# Dev_BRD_STM32F030F4P6TR.net
KiCad netlist of a schematic drawn in Altium Designer
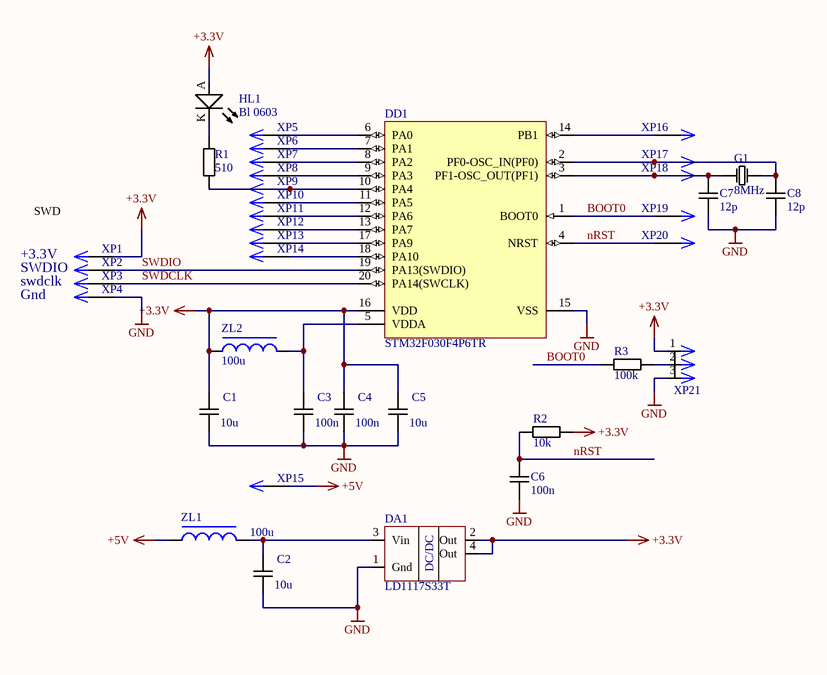
[diagram p0: Dev_BRD_STM32F030F4P6TR.SchDoc]

(export (version "E")
  (design (tool "Eeschema 10.0.6"))
  (components
    (comp (ref "C1")
      (value "10u")
      (footprint "CAPC1608(0603)N")
      (description "?")
      (fields (field (name "PART NUMBER") "CAPC1608(0603)"))
      (libsource (lib "SssAccesDatbase") (part "Cap"))
    )
    (comp (ref "C2")
      (value "10u")
      (footprint "CAPC1608(0603)N")
      (description "?")
      (fields (field (name "PART NUMBER") "CAPC1608(0603)"))
      (libsource (lib "SssAccesDatbase") (part "Cap"))
    )
    (comp (ref "C3")
      (value "100n")
      (footprint "CAPC1608(0603)N")
      (description "?")
      (fields (field (name "PART NUMBER") "CAPC1608(0603)"))
      (libsource (lib "SssAccesDatbase") (part "Cap"))
    )
    (comp (ref "C4")
      (value "100n")
      (footprint "CAPC1608(0603)N")
      (description "?")
      (fields (field (name "PART NUMBER") "CAPC1608(0603)"))
      (libsource (lib "SssAccesDatbase") (part "Cap"))
    )
    (comp (ref "C5")
      (value "10u")
      (footprint "CAPC1608(0603)N")
      (description "?")
      (fields (field (name "PART NUMBER") "CAPC1608(0603)"))
      (libsource (lib "SssAccesDatbase") (part "Cap"))
    )
    (comp (ref "C6")
      (value "100n")
      (footprint "CAPC1608(0603)N")
      (description "?")
      (fields (field (name "PART NUMBER") "CAPC1608(0603)"))
      (libsource (lib "SssAccesDatbase") (part "Cap"))
    )
    (comp (ref "C7")
      (value "12p")
      (footprint "CAPC1608(0603)N")
      (description "?")
      (fields (field (name "PART NUMBER") "CAPC1608(0603)"))
      (libsource (lib "SssAccesDatbase") (part "Cap"))
    )
    (comp (ref "C8")
      (value "12p")
      (footprint "CAPC1608(0603)N")
      (description "?")
      (fields (field (name "PART NUMBER") "CAPC1608(0603)"))
      (libsource (lib "SssAccesDatbase") (part "Cap"))
    )
    (comp (ref "DA1")
      (value "LD1117S33T")
      (footprint "SOT223_M")
      (description "LDO Voltage Regulators 3.3V 0.8A Positive")
      (fields (field (name "DIGI-KEY PART NUMBER") "?"))
      (libsource (lib "SssAccesDatbase") (part "LD1117S33T"))
    )
    (comp (ref "DD1")
      (value "STM32F030F4P6TR")
      (footprint "STM-TSSOP20_M")
      (description "ARM Microcontrollers - MCU Entry-level ARM Cortex-M0 Value MCU")
      (fields
        (field (name "PARTNUMBER") "STM32F030F4P6")
        (field (name "MOUSER PART NUMBER") "511-STM32F030F4P6TR")
      )
      (libsource (lib "SssAccesDatbase") (part "STM32F030F4P6"))
    )
    (comp (ref "G1")
      (value "8MHz")
      (footprint "HC-49/S")
      (description "Crystal HC-49/S")
      (libsource (lib "SssAccesDatbase") (part "Crystal"))
    )
    (comp (ref "HL1")
      (value "Bl 0603")
      (footprint "LED-0603-BLUE")
      (description "LED BLUE DIFFUSED 0603 SMD")
      (fields
        (field (name "PART NUMBER") "150060BS55040")
        (field (name "DIGI-KEY PART NUMBER") "732-12013-1-ND")
      )
      (libsource (lib "SssAccesDatbase") (part "LED"))
    )
    (comp (ref "R1")
      (value "510")
      (footprint "RESC1608(0603)N")
      (fields (field (name "PART NUMBER") "RESC1608(0603)") (field (name "DIGI-KEY PART NUMBER") "???"))
      (libsource (lib "") (part "Resistor general_2"))
    )
    (comp (ref "R2")
      (value "10k")
      (footprint "RESC1608(0603)N")
      (fields (field (name "PART NUMBER") "RESC1608(0603)") (field (name "DIGI-KEY PART NUMBER") "???"))
      (libsource (lib "SssAccesDatbase") (part "Resistor general"))
    )
    (comp (ref "R3")
      (value "100k")
      (footprint "RESC1608(0603)N")
      (fields (field (name "PART NUMBER") "RESC1608(0603)") (field (name "DIGI-KEY PART NUMBER") "???"))
      (libsource (lib "") (part "Resistor general_1"))
    )
    (comp (ref "XP1")
      (value "PLS-1")
      (footprint "PLS-1-3D")
      (description "CONN HEADER VERT 1POS")
      (fields
        (field (name "DIGI-KEY PART NUMBER") "S1011EC-01-ND")
        (field (name "MANUFACTURER PART NUMBER") "PRPC001SAAN-RC")
      )
      (libsource (lib "SssAccesDatbase") (part "XP-1_1"))
    )
    (comp (ref "XP2")
      (value "PLS-1")
      (footprint "PLS-1-3D")
      (description "CONN HEADER VERT 1POS")
      (fields
        (field (name "DIGI-KEY PART NUMBER") "S1011EC-01-ND")
        (field (name "MANUFACTURER PART NUMBER") "PRPC001SAAN-RC")
      )
      (libsource (lib "SssAccesDatbase") (part "XP-1_1"))
    )
    (comp (ref "XP3")
      (value "PLS-1")
      (footprint "PLS-1-3D")
      (description "CONN HEADER VERT 1POS")
      (fields
        (field (name "DIGI-KEY PART NUMBER") "S1011EC-01-ND")
        (field (name "MANUFACTURER PART NUMBER") "PRPC001SAAN-RC")
      )
      (libsource (lib "SssAccesDatbase") (part "XP-1_1"))
    )
    (comp (ref "XP4")
      (value "PLS-1")
      (footprint "PLS-1-3D")
      (description "CONN HEADER VERT 1POS")
      (fields
        (field (name "DIGI-KEY PART NUMBER") "S1011EC-01-ND")
        (field (name "MANUFACTURER PART NUMBER") "PRPC001SAAN-RC")
      )
      (libsource (lib "SssAccesDatbase") (part "XP-1_1"))
    )
    (comp (ref "XP5")
      (value "PLS-1")
      (footprint "PLS-1-3D")
      (description "CONN HEADER VERT 1POS")
      (fields
        (field (name "DIGI-KEY PART NUMBER") "S1011EC-01-ND")
        (field (name "MANUFACTURER PART NUMBER") "PRPC001SAAN-RC")
      )
      (libsource (lib "SssAccesDatbase") (part "XP-1_1"))
    )
    (comp (ref "XP6")
      (value "PLS-1")
      (footprint "PLS-1-3D")
      (description "CONN HEADER VERT 1POS")
      (fields
        (field (name "DIGI-KEY PART NUMBER") "S1011EC-01-ND")
        (field (name "MANUFACTURER PART NUMBER") "PRPC001SAAN-RC")
      )
      (libsource (lib "SssAccesDatbase") (part "XP-1_1"))
    )
    (comp (ref "XP7")
      (value "PLS-1")
      (footprint "PLS-1-3D")
      (description "CONN HEADER VERT 1POS")
      (fields
        (field (name "DIGI-KEY PART NUMBER") "S1011EC-01-ND")
        (field (name "MANUFACTURER PART NUMBER") "PRPC001SAAN-RC")
      )
      (libsource (lib "SssAccesDatbase") (part "XP-1_1"))
    )
    (comp (ref "XP8")
      (value "PLS-1")
      (footprint "PLS-1-3D")
      (description "CONN HEADER VERT 1POS")
      (fields
        (field (name "DIGI-KEY PART NUMBER") "S1011EC-01-ND")
        (field (name "MANUFACTURER PART NUMBER") "PRPC001SAAN-RC")
      )
      (libsource (lib "SssAccesDatbase") (part "XP-1_1"))
    )
    (comp (ref "XP9")
      (value "PLS-1")
      (footprint "PLS-1-3D")
      (description "CONN HEADER VERT 1POS")
      (fields
        (field (name "DIGI-KEY PART NUMBER") "S1011EC-01-ND")
        (field (name "MANUFACTURER PART NUMBER") "PRPC001SAAN-RC")
      )
      (libsource (lib "SssAccesDatbase") (part "XP-1_1"))
    )
    (comp (ref "XP10")
      (value "PLS-1")
      (footprint "PLS-1-3D")
      (description "CONN HEADER VERT 1POS")
      (fields
        (field (name "DIGI-KEY PART NUMBER") "S1011EC-01-ND")
        (field (name "MANUFACTURER PART NUMBER") "PRPC001SAAN-RC")
      )
      (libsource (lib "SssAccesDatbase") (part "XP-1_1"))
    )
    (comp (ref "XP11")
      (value "PLS-1")
      (footprint "PLS-1-3D")
      (description "CONN HEADER VERT 1POS")
      (fields
        (field (name "DIGI-KEY PART NUMBER") "S1011EC-01-ND")
        (field (name "MANUFACTURER PART NUMBER") "PRPC001SAAN-RC")
      )
      (libsource (lib "SssAccesDatbase") (part "XP-1_1"))
    )
    (comp (ref "XP12")
      (value "PLS-1")
      (footprint "PLS-1-3D")
      (description "CONN HEADER VERT 1POS")
      (fields
        (field (name "DIGI-KEY PART NUMBER") "S1011EC-01-ND")
        (field (name "MANUFACTURER PART NUMBER") "PRPC001SAAN-RC")
      )
      (libsource (lib "SssAccesDatbase") (part "XP-1_1"))
    )
    (comp (ref "XP13")
      (value "PLS-1")
      (footprint "PLS-1-3D")
      (description "CONN HEADER VERT 1POS")
      (fields
        (field (name "DIGI-KEY PART NUMBER") "S1011EC-01-ND")
        (field (name "MANUFACTURER PART NUMBER") "PRPC001SAAN-RC")
      )
      (libsource (lib "SssAccesDatbase") (part "XP-1_1"))
    )
    (comp (ref "XP14")
      (value "PLS-1")
      (footprint "PLS-1-3D")
      (description "CONN HEADER VERT 1POS")
      (fields
        (field (name "DIGI-KEY PART NUMBER") "S1011EC-01-ND")
        (field (name "MANUFACTURER PART NUMBER") "PRPC001SAAN-RC")
      )
      (libsource (lib "SssAccesDatbase") (part "XP-1_1"))
    )
    (comp (ref "XP15")
      (value "PLS-1")
      (footprint "PLS-1-3D")
      (description "CONN HEADER VERT 1POS")
      (fields
        (field (name "DIGI-KEY PART NUMBER") "S1011EC-01-ND")
        (field (name "MANUFACTURER PART NUMBER") "PRPC001SAAN-RC")
      )
      (libsource (lib "SssAccesDatbase") (part "XP-1_1"))
    )
    (comp (ref "XP16")
      (value "PLS-1")
      (footprint "PLS-1-3D")
      (description "CONN HEADER VERT 1POS")
      (fields
        (field (name "DIGI-KEY PART NUMBER") "S1011EC-01-ND")
        (field (name "MANUFACTURER PART NUMBER") "PRPC001SAAN-RC")
      )
      (libsource (lib "SssAccesDatbase") (part "XP-1_1"))
    )
    (comp (ref "XP17")
      (value "PLS-1")
      (footprint "PLS-1-3D")
      (description "CONN HEADER VERT 1POS")
      (fields
        (field (name "DIGI-KEY PART NUMBER") "S1011EC-01-ND")
        (field (name "MANUFACTURER PART NUMBER") "PRPC001SAAN-RC")
      )
      (libsource (lib "SssAccesDatbase") (part "XP-1_1"))
    )
    (comp (ref "XP18")
      (value "PLS-1")
      (footprint "PLS-1-3D")
      (description "CONN HEADER VERT 1POS")
      (fields
        (field (name "DIGI-KEY PART NUMBER") "S1011EC-01-ND")
        (field (name "MANUFACTURER PART NUMBER") "PRPC001SAAN-RC")
      )
      (libsource (lib "SssAccesDatbase") (part "XP-1_1"))
    )
    (comp (ref "XP19")
      (value "PLS-1")
      (footprint "PLS-1-3D")
      (description "CONN HEADER VERT 1POS")
      (fields
        (field (name "DIGI-KEY PART NUMBER") "S1011EC-01-ND")
        (field (name "MANUFACTURER PART NUMBER") "PRPC001SAAN-RC")
      )
      (libsource (lib "SssAccesDatbase") (part "XP-1_1"))
    )
    (comp (ref "XP20")
      (value "PLS-1")
      (footprint "PLS-1-3D")
      (description "CONN HEADER VERT 1POS")
      (fields
        (field (name "DIGI-KEY PART NUMBER") "S1011EC-01-ND")
        (field (name "MANUFACTURER PART NUMBER") "PRPC001SAAN-RC")
      )
      (libsource (lib "SssAccesDatbase") (part "XP-1_1"))
    )
    (comp (ref "XP21")
      (value "PLS-3")
      (footprint "PLS-3-3D")
      (description "CONN HEADER VERT 3POS 2.54MM")
      (fields (field (name "PART NUMBER") "PR20203VBNN") (field (name "DIGI-KEY PART NUMBER") "1849-1003-ND"))
      (libsource (lib "SssAccesDatbase") (part "XP-3_Jump"))
    )
    (comp (ref "ZL1")
      (value "100u")
      (footprint "INDC1608(0603)N")
      (description "ferite bead")
      (fields (field (name "PART NUMBER") "Ferite1608(0603)") (field (name "DIGI-KEY PART NUMBER") "???"))
      (libsource (lib "SssAccesDatbase") (part "ZL"))
    )
    (comp (ref "ZL2")
      (value "100u")
      (footprint "INDC1608(0603)N")
      (description "ferite bead")
      (fields (field (name "PART NUMBER") "Ferite1608(0603)") (field (name "DIGI-KEY PART NUMBER") "???"))
      (libsource (lib "SssAccesDatbase") (part "ZL"))
    )
  )
  (nets
    (net (code "1") (name "+3.3V") (class "Default")
      (node (ref "C1") (pin "2") (pinfunction "2_2") (pintype "passive"))
      (node (ref "C4") (pin "2") (pinfunction "2_2") (pintype "passive"))
      (node (ref "C5") (pin "2") (pinfunction "2_2") (pintype "passive"))
      (node (ref "DA1") (pin "2") (pinfunction "Out_2") (pintype "passive"))
      (node (ref "DA1") (pin "4") (pinfunction "Out_4") (pintype "passive"))
      (node (ref "DD1") (pin "16") (pinfunction "VDD_16") (pintype "power_in"))
      (node (ref "HL1") (pin "A") (pinfunction "A_A") (pintype "passive"))
      (node (ref "R2") (pin "2") (pinfunction "2_2") (pintype "passive"))
      (node (ref "XP1") (pin "1") (pinfunction "1_1") (pintype "passive"))
      (node (ref "XP21") (pin "1") (pinfunction "1_1") (pintype "passive"))
      (node (ref "ZL2") (pin "1") (pinfunction "1_1") (pintype "passive"))
    )
    (net (code "2") (name "+5V") (class "Default")
      (node (ref "XP15") (pin "1") (pinfunction "1_1") (pintype "passive"))
      (node (ref "ZL1") (pin "1") (pinfunction "1_1") (pintype "passive"))
    )
    (net (code "3") (name "/BOOT0") (class "Default")
      (node (ref "DD1") (pin "1") (pinfunction "BOOT0_1") (pintype "input"))
      (node (ref "R3") (pin "1") (pinfunction "1_1") (pintype "passive"))
      (node (ref "XP19") (pin "1") (pinfunction "1_1") (pintype "passive"))
    )
    (net (code "4") (name "/SWDCLK") (class "Default")
      (node (ref "DD1") (pin "20") (pinfunction "PA14(SWCLK)_20") (pintype "bidirectional"))
      (node (ref "XP3") (pin "1") (pinfunction "1_1") (pintype "passive"))
    )
    (net (code "5") (name "/SWDIO") (class "Default")
      (node (ref "DD1") (pin "19") (pinfunction "PA13(SWDIO)_19") (pintype "bidirectional"))
      (node (ref "XP2") (pin "1") (pinfunction "1_1") (pintype "passive"))
    )
    (net (code "6") (name "/nRST") (class "Default")
      (node (ref "C6") (pin "2") (pinfunction "2_2") (pintype "passive"))
      (node (ref "DD1") (pin "4") (pinfunction "NRST_4") (pintype "bidirectional"))
      (node (ref "R2") (pin "1") (pinfunction "1_1") (pintype "passive"))
      (node (ref "XP20") (pin "1") (pinfunction "1_1") (pintype "passive"))
    )
    (net (code "7") (name "GND") (class "Default")
      (node (ref "C1") (pin "1") (pinfunction "1_1") (pintype "passive"))
      (node (ref "C2") (pin "1") (pinfunction "1_1") (pintype "passive"))
      (node (ref "C3") (pin "1") (pinfunction "1_1") (pintype "passive"))
      (node (ref "C4") (pin "1") (pinfunction "1_1") (pintype "passive"))
      (node (ref "C5") (pin "1") (pinfunction "1_1") (pintype "passive"))
      (node (ref "C6") (pin "1") (pinfunction "1_1") (pintype "passive"))
      (node (ref "C7") (pin "1") (pinfunction "1_1") (pintype "passive"))
      (node (ref "C8") (pin "1") (pinfunction "1_1") (pintype "passive"))
      (node (ref "DA1") (pin "1") (pinfunction "Gnd_1") (pintype "passive"))
      (node (ref "DD1") (pin "15") (pinfunction "VSS_15") (pintype "power_in"))
      (node (ref "XP21") (pin "3") (pinfunction "3_3") (pintype "passive"))
      (node (ref "XP4") (pin "1") (pinfunction "1_1") (pintype "passive"))
    )
    (net (code "8") (name "Net-(DA1-Vin)") (class "Default")
      (node (ref "C2") (pin "2") (pinfunction "2_2") (pintype "passive"))
      (node (ref "DA1") (pin "3") (pinfunction "Vin_3") (pintype "passive"))
      (node (ref "ZL1") (pin "2") (pinfunction "2_2") (pintype "passive"))
    )
    (net (code "9") (name "Net-(DD1-PA0)") (class "Default")
      (node (ref "DD1") (pin "6") (pinfunction "PA0_6") (pintype "bidirectional"))
      (node (ref "XP5") (pin "1") (pinfunction "1_1") (pintype "passive"))
    )
    (net (code "10") (name "Net-(DD1-PA1)") (class "Default")
      (node (ref "DD1") (pin "7") (pinfunction "PA1_7") (pintype "bidirectional"))
      (node (ref "XP6") (pin "1") (pinfunction "1_1") (pintype "passive"))
    )
    (net (code "11") (name "Net-(DD1-PA2)") (class "Default")
      (node (ref "DD1") (pin "8") (pinfunction "PA2_8") (pintype "bidirectional"))
      (node (ref "XP7") (pin "1") (pinfunction "1_1") (pintype "passive"))
    )
    (net (code "12") (name "Net-(DD1-PA3)") (class "Default")
      (node (ref "DD1") (pin "9") (pinfunction "PA3_9") (pintype "bidirectional"))
      (node (ref "XP8") (pin "1") (pinfunction "1_1") (pintype "passive"))
    )
    (net (code "13") (name "Net-(DD1-PA4)") (class "Default")
      (node (ref "DD1") (pin "10") (pinfunction "PA4_10") (pintype "bidirectional"))
      (node (ref "R1") (pin "2") (pinfunction "2_2") (pintype "passive"))
      (node (ref "XP9") (pin "1") (pinfunction "1_1") (pintype "passive"))
    )
    (net (code "14") (name "Net-(DD1-PA5)") (class "Default")
      (node (ref "DD1") (pin "11") (pinfunction "PA5_11") (pintype "bidirectional"))
      (node (ref "XP10") (pin "1") (pinfunction "1_1") (pintype "passive"))
    )
    (net (code "15") (name "Net-(DD1-PA6)") (class "Default")
      (node (ref "DD1") (pin "12") (pinfunction "PA6_12") (pintype "bidirectional"))
      (node (ref "XP11") (pin "1") (pinfunction "1_1") (pintype "passive"))
    )
    (net (code "16") (name "Net-(DD1-PA7)") (class "Default")
      (node (ref "DD1") (pin "13") (pinfunction "PA7_13") (pintype "bidirectional"))
      (node (ref "XP12") (pin "1") (pinfunction "1_1") (pintype "passive"))
    )
    (net (code "17") (name "Net-(DD1-PA9)") (class "Default")
      (node (ref "DD1") (pin "17") (pinfunction "PA9_17") (pintype "bidirectional"))
      (node (ref "XP13") (pin "1") (pinfunction "1_1") (pintype "passive"))
    )
    (net (code "18") (name "Net-(DD1-PA10)") (class "Default")
      (node (ref "DD1") (pin "18") (pinfunction "PA10_18") (pintype "bidirectional"))
      (node (ref "XP14") (pin "1") (pinfunction "1_1") (pintype "passive"))
    )
    (net (code "19") (name "Net-(DD1-PB1)") (class "Default")
      (node (ref "DD1") (pin "14") (pinfunction "PB1_14") (pintype "bidirectional"))
      (node (ref "XP16") (pin "1") (pinfunction "1_1") (pintype "passive"))
    )
    (net (code "20") (name "Net-(DD1-PF0-OSC_IN(PF0))") (class "Default")
      (node (ref "C8") (pin "2") (pinfunction "2_2") (pintype "passive"))
      (node (ref "DD1") (pin "2") (pinfunction "PF0-OSC_IN(PF0)_2") (pintype "bidirectional"))
      (node (ref "G1") (pin "2") (pinfunction "2_2") (pintype "passive"))
      (node (ref "XP17") (pin "1") (pinfunction "1_1") (pintype "passive"))
    )
    (net (code "21") (name "Net-(DD1-PF1-OSC_OUT(PF1))") (class "Default")
      (node (ref "C7") (pin "2") (pinfunction "2_2") (pintype "passive"))
      (node (ref "DD1") (pin "3") (pinfunction "PF1-OSC_OUT(PF1)_3") (pintype "bidirectional"))
      (node (ref "G1") (pin "1") (pinfunction "1_1") (pintype "passive"))
      (node (ref "XP18") (pin "1") (pinfunction "1_1") (pintype "passive"))
    )
    (net (code "22") (name "Net-(DD1-VDDA)") (class "Default")
      (node (ref "C3") (pin "2") (pinfunction "2_2") (pintype "passive"))
      (node (ref "DD1") (pin "5") (pinfunction "VDDA_5") (pintype "power_in"))
      (node (ref "ZL2") (pin "2") (pinfunction "2_2") (pintype "passive"))
    )
    (net (code "23") (name "Net-(HL1-PadK)") (class "Default")
      (node (ref "HL1") (pin "K") (pinfunction "K_K") (pintype "passive"))
      (node (ref "R1") (pin "1") (pinfunction "1_1") (pintype "passive"))
    )
    (net (code "24") (name "Net-(R3-Pad2)") (class "Default")
      (node (ref "R3") (pin "2") (pinfunction "2_2") (pintype "passive"))
      (node (ref "XP21") (pin "2") (pinfunction "2_2") (pintype "passive"))
    )
  )
)
